# Lumiboard_-_sensor_module_rev_B.net
KiCad netlist of a schematic drawn in EAGLE
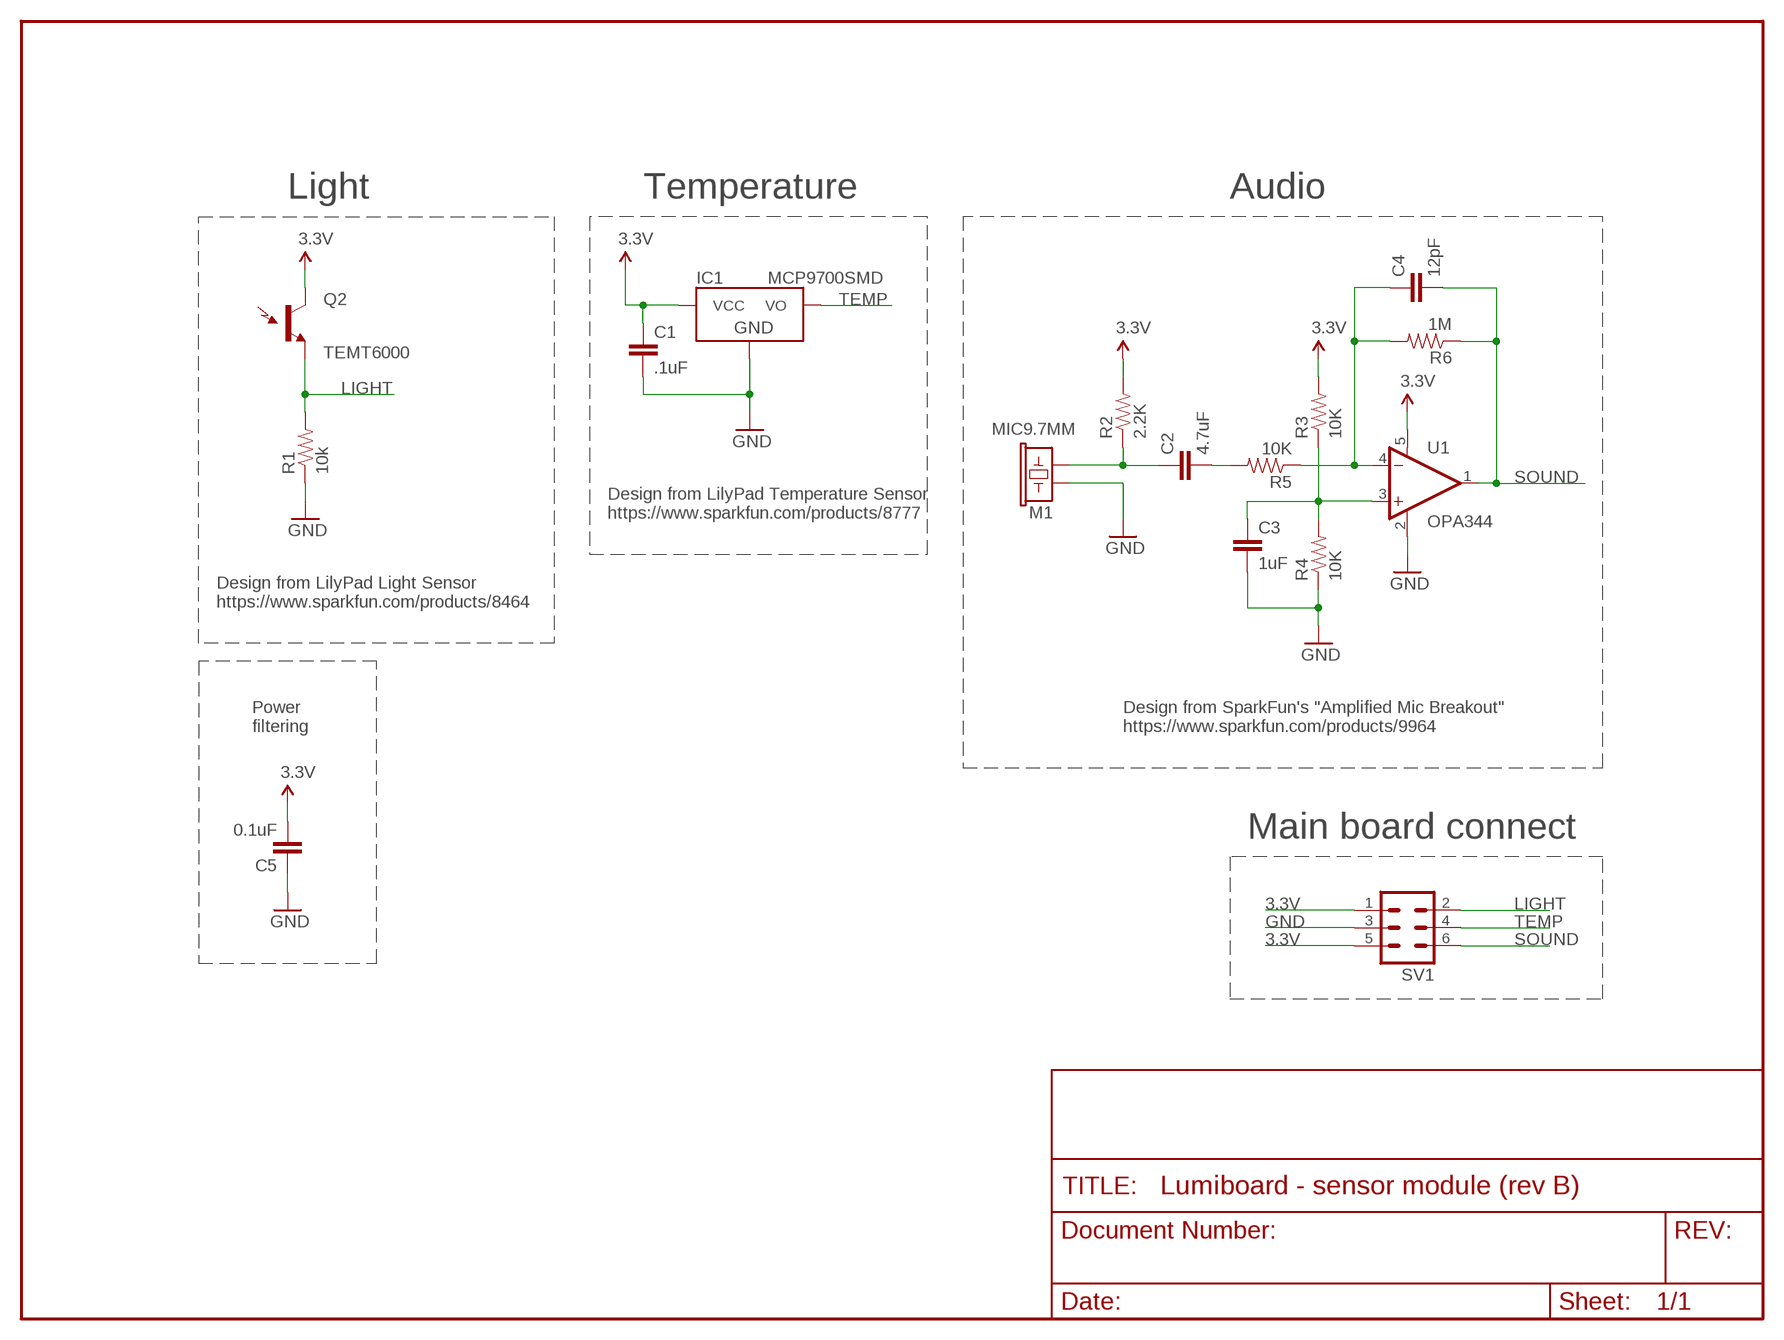
[diagram p0: schematic, sheet 1]

(export (version "E")
  (design (tool "Eeschema 10.0.6"))
  (components
    (comp (ref "C1")
      (value ".1uF")
      (footprint "eagle-import:0805")
      (libsource (lib "eagle-import") (part "CAP0805"))
    )
    (comp (ref "C2")
      (value "4.7uF")
      (footprint "eagle-import:0805")
      (libsource (lib "eagle-import") (part "SparkFun-Capacitors_CAP0805"))
    )
    (comp (ref "C3")
      (value "1uF")
      (footprint "eagle-import:0805")
      (libsource (lib "eagle-import") (part "SparkFun-Capacitors_CAP0805"))
    )
    (comp (ref "C4")
      (value "12pF")
      (footprint "eagle-import:0805")
      (libsource (lib "eagle-import") (part "SparkFun-Capacitors_CAP0805"))
    )
    (comp (ref "C5")
      (value "0.1uF")
      (footprint "eagle-import:0805")
      (libsource (lib "eagle-import") (part "SparkFun-Capacitors_CAP0805"))
    )
    (comp (ref "IC1")
      (value "MCP9700SMD")
      (footprint "eagle-import:SOT23-3")
      (libsource (lib "eagle-import") (part "MCP9700SMD"))
    )
    (comp (ref "M1")
      (value "MIC9.7MM")
      (footprint "eagle-import:MIC-9.7MM")
      (libsource (lib "eagle-import") (part "MIC9.7MM"))
    )
    (comp (ref "Q2")
      (value "TEMT6000")
      (footprint "eagle-import:TEMT6000-SEN")
      (libsource (lib "eagle-import") (part "TEMT6000"))
    )
    (comp (ref "R1")
      (value "10k")
      (footprint "eagle-import:0805")
      (libsource (lib "eagle-import") (part "RESISTOR0805-RES"))
    )
    (comp (ref "R2")
      (value "2.2K")
      (footprint "eagle-import:0805")
      (libsource (lib "eagle-import") (part "RESISTOR0805-RES"))
    )
    (comp (ref "R3")
      (value "10K")
      (footprint "eagle-import:0805")
      (libsource (lib "eagle-import") (part "RESISTOR0805-RES"))
    )
    (comp (ref "R4")
      (value "10K")
      (footprint "eagle-import:0805")
      (libsource (lib "eagle-import") (part "RESISTOR0805-RES"))
    )
    (comp (ref "R5")
      (value "10K")
      (footprint "eagle-import:0805")
      (libsource (lib "eagle-import") (part "RESISTOR0805-RES"))
    )
    (comp (ref "R6")
      (value "1M")
      (footprint "eagle-import:0805")
      (libsource (lib "eagle-import") (part "RESISTOR0805-RES"))
    )
    (comp (ref "SV1")
      (value "ML6")
      (footprint "eagle-import:ML6")
      (libsource (lib "eagle-import") (part "ML6"))
    )
    (comp (ref "U1")
      (value "OPA344")
      (footprint "eagle-import:SOT23-5")
      (libsource (lib "eagle-import") (part "OPA344"))
    )
  )
  (nets
    (net (code "1") (name "/LIGHT") (class "Default")
      (node (ref "Q2") (pin "EMITTER") (pinfunction "E1_EMITTER") (pintype "passive"))
      (node (ref "R1") (pin "2") (pinfunction "2_2") (pintype "passive"))
      (node (ref "SV1") (pin "2") (pinfunction "2_2") (pintype "passive"))
    )
    (net (code "2") (name "/SOUND") (class "Default")
      (node (ref "C4") (pin "2") (pinfunction "2_2") (pintype "passive"))
      (node (ref "R6") (pin "1") (pinfunction "1_1") (pintype "passive"))
      (node (ref "SV1") (pin "6") (pinfunction "6_6") (pintype "passive"))
      (node (ref "U1") (pin "1") (pinfunction "OUT_1") (pintype "output"))
    )
    (net (code "3") (name "/TEMP") (class "Default")
      (node (ref "IC1") (pin "2") (pinfunction "VO_2") (pintype "bidirectional"))
      (node (ref "SV1") (pin "4") (pinfunction "4_4") (pintype "passive"))
    )
    (net (code "4") (name "3.3V") (class "Default")
      (node (ref "C1") (pin "1") (pinfunction "1_1") (pintype "passive"))
      (node (ref "C5") (pin "2") (pinfunction "2_2") (pintype "passive"))
      (node (ref "IC1") (pin "1") (pinfunction "VCC_1") (pintype "bidirectional"))
      (node (ref "Q2") (pin "COLLECTOR") (pinfunction "C1_COLLECTOR") (pintype "passive"))
      (node (ref "R2") (pin "2") (pinfunction "2_2") (pintype "passive"))
      (node (ref "R3") (pin "2") (pinfunction "2_2") (pintype "passive"))
      (node (ref "SV1") (pin "1") (pinfunction "1_1") (pintype "passive"))
      (node (ref "SV1") (pin "5") (pinfunction "5_5") (pintype "passive"))
      (node (ref "U1") (pin "5") (pinfunction "V+_5") (pintype "power_in"))
    )
    (net (code "5") (name "GND") (class "Default")
      (node (ref "C1") (pin "2") (pinfunction "2_2") (pintype "passive"))
      (node (ref "C3") (pin "2") (pinfunction "2_2") (pintype "passive"))
      (node (ref "C5") (pin "1") (pinfunction "1_1") (pintype "passive"))
      (node (ref "IC1") (pin "3") (pinfunction "GND_3") (pintype "bidirectional"))
      (node (ref "M1") (pin "2") (pinfunction "2_2") (pintype "passive"))
      (node (ref "R1") (pin "1") (pinfunction "1_1") (pintype "passive"))
      (node (ref "R4") (pin "1") (pinfunction "1_1") (pintype "passive"))
      (node (ref "SV1") (pin "3") (pinfunction "3_3") (pintype "passive"))
      (node (ref "U1") (pin "2") (pinfunction "V-_2") (pintype "power_in"))
    )
    (net (code "6") (name "Net-(C2-Pad1)") (class "Default")
      (node (ref "C2") (pin "1") (pinfunction "1_1") (pintype "passive"))
      (node (ref "M1") (pin "1") (pinfunction "1_1") (pintype "passive"))
      (node (ref "R2") (pin "1") (pinfunction "1_1") (pintype "passive"))
    )
    (net (code "7") (name "Net-(C2-Pad2)") (class "Default")
      (node (ref "C2") (pin "2") (pinfunction "2_2") (pintype "passive"))
      (node (ref "R5") (pin "2") (pinfunction "2_2") (pintype "passive"))
    )
    (net (code "8") (name "Net-(U1-+IN)") (class "Default")
      (node (ref "C3") (pin "1") (pinfunction "1_1") (pintype "passive"))
      (node (ref "R3") (pin "1") (pinfunction "1_1") (pintype "passive"))
      (node (ref "R4") (pin "2") (pinfunction "2_2") (pintype "passive"))
      (node (ref "U1") (pin "3") (pinfunction "+IN_3") (pintype "input"))
    )
    (net (code "9") (name "Net-(U1--IN)") (class "Default")
      (node (ref "C4") (pin "1") (pinfunction "1_1") (pintype "passive"))
      (node (ref "R5") (pin "1") (pinfunction "1_1") (pintype "passive"))
      (node (ref "R6") (pin "2") (pinfunction "2_2") (pintype "passive"))
      (node (ref "U1") (pin "4") (pinfunction "-IN_4") (pintype "input"))
    )
  )
)
